# LCD.net
KiCad netlist of a schematic drawn in Altium Designer
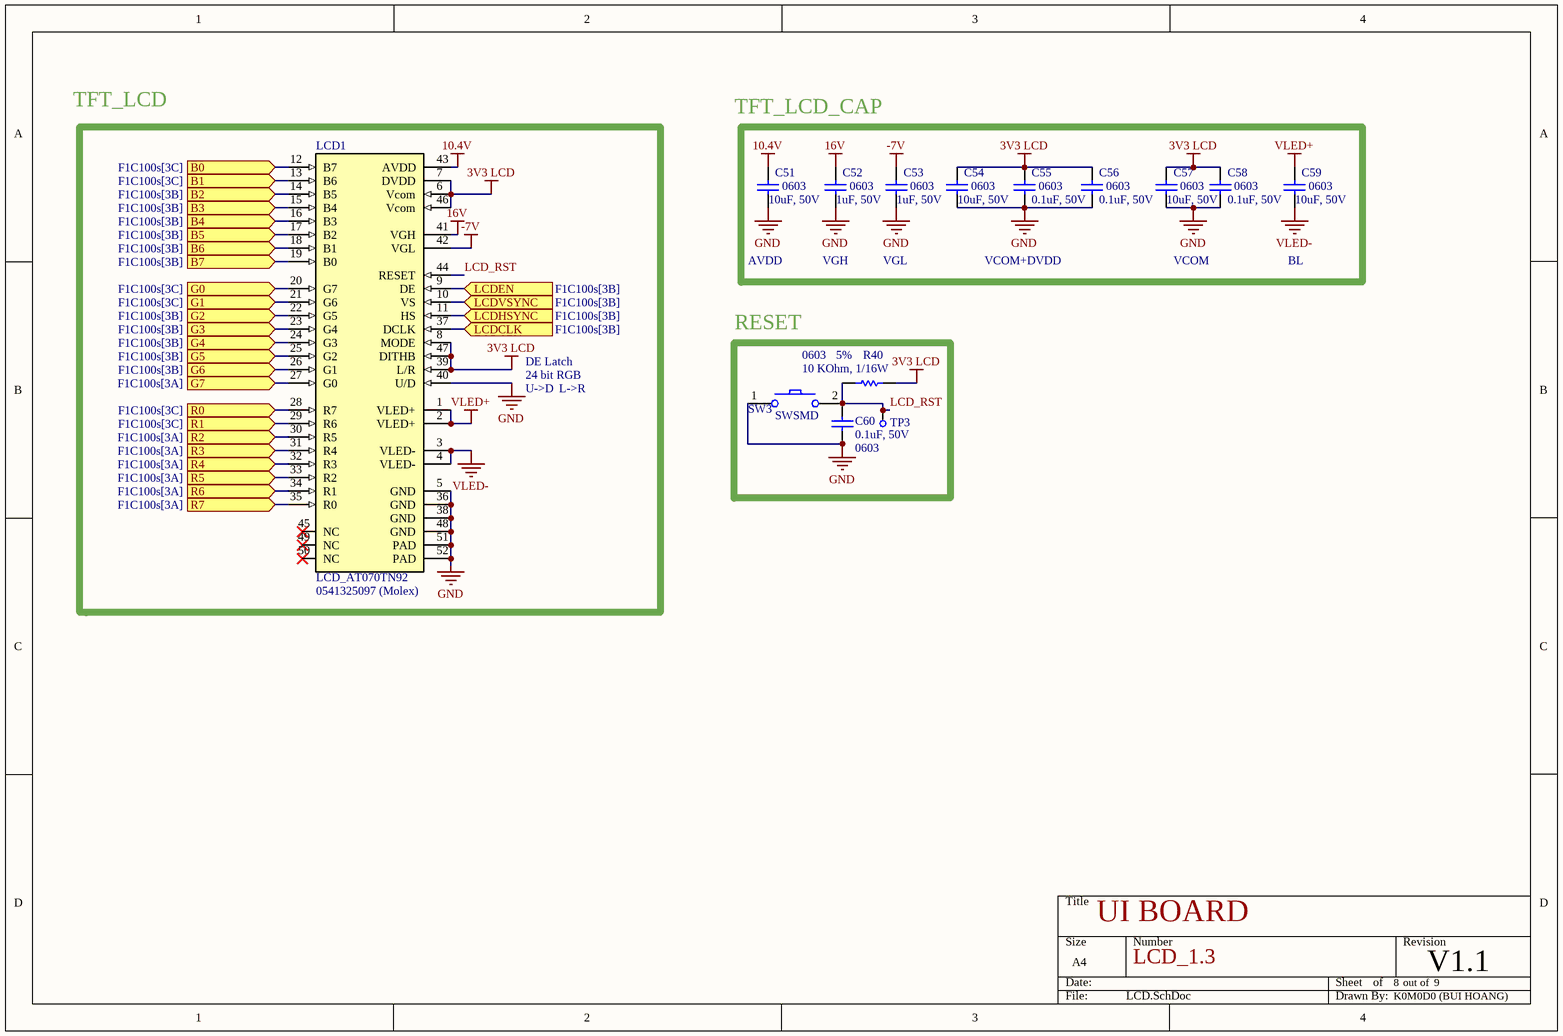
[diagram p0: LCD.SchDoc]

(export (version "E")
  (design (tool "Eeschema 10.0.6"))
  (components
    (comp (ref "C51")
      (value "10uF, 50V")
      (footprint "C_0603")
      (description "CAP_0603")
      (fields (field (name "PACKAGE") "0603"))
      (libsource (lib "DisplayLib") (part "CAP_0603"))
    )
    (comp (ref "C52")
      (value "1uF, 50V")
      (footprint "C_0603")
      (description "CAP_0603")
      (fields (field (name "PACKAGE") "0603"))
      (libsource (lib "DisplayLib") (part "CAP_0603"))
    )
    (comp (ref "C53")
      (value "1uF, 50V")
      (footprint "C_0603")
      (description "CAP_0603")
      (fields (field (name "PACKAGE") "0603"))
      (libsource (lib "DisplayLib") (part "CAP_0603"))
    )
    (comp (ref "C54")
      (value "10uF, 50V")
      (footprint "C_0603")
      (description "CAP_0603")
      (fields (field (name "PACKAGE") "0603"))
      (libsource (lib "DisplayLib") (part "CAP_0603"))
    )
    (comp (ref "C55")
      (value "0.1uF, 50V")
      (footprint "C_0603")
      (description "CAP_0603")
      (fields (field (name "PACKAGE") "0603"))
      (libsource (lib "DisplayLib") (part "CAP_0603"))
    )
    (comp (ref "C56")
      (value "0.1uF, 50V")
      (footprint "C_0603")
      (description "CAP_0603")
      (fields (field (name "PACKAGE") "0603"))
      (libsource (lib "DisplayLib") (part "CAP_0603"))
    )
    (comp (ref "C57")
      (value "10uF, 50V")
      (footprint "C_0603")
      (description "CAP_0603")
      (fields (field (name "PACKAGE") "0603"))
      (libsource (lib "DisplayLib") (part "CAP_0603"))
    )
    (comp (ref "C58")
      (value "0.1uF, 50V")
      (footprint "C_0603")
      (description "CAP_0603")
      (fields (field (name "PACKAGE") "0603"))
      (libsource (lib "DisplayLib") (part "CAP_0603"))
    )
    (comp (ref "C59")
      (value "10uF, 50V")
      (footprint "C_0603")
      (description "CAP_0603")
      (fields (field (name "PACKAGE") "0603"))
      (libsource (lib "DisplayLib") (part "CAP_0603"))
    )
    (comp (ref "C60")
      (value "0.1uF, 50V")
      (footprint "C_0603")
      (description "CAP_0603")
      (fields (field (name "PACKAGE") "0603"))
      (libsource (lib "DisplayLib") (part "CAP_0603"))
    )
    (comp (ref "LCD1")
      (value "LCD_AT070TN92")
      (footprint "CONN_LCD_AT070TN90")
      (description "LCD 7 inch (800 x 3(RGB) x 480) RES\r\n__NOTE THAT THIS IS FFC 50PINS CONN w/ THE LCD FOOTPRINT!__")
      (fields (field (name "CONNECTOR PART NUMBER") "0541325097 (Molex)"))
      (libsource (lib "DisplayLib") (part "LCD_AT070TN92"))
    )
    (comp (ref "R40")
      (value "10 KOhm, 1/16W")
      (footprint "R_0603")
      (description "RES_0603")
      (fields (field (name "PACKAGE") "0603") (field (name "ACC") "5%"))
      (libsource (lib "DisplayLib") (part "RES_0603"))
    )
    (comp (ref "SW3")
      (value "SWSMD")
      (footprint "SW_SMD_NOGND")
      (description "SW_SMD")
      (libsource (lib "DisplayLib") (part "SWSMD_NOGND"))
    )
    (comp (ref "TP3")
      (value "TESTPT")
      (footprint "TESTPT")
      (description "Test point")
      (libsource (lib "DisplayLib") (part "TESTPT"))
    )
  )
  (nets
    (net (code "1") (name "-7V") (class "Default")
      (node (ref "C53") (pin "2") (pinfunction "2_2") (pintype "passive"))
      (node (ref "LCD1") (pin "42") (pinfunction "VGL_42") (pintype "power_in"))
    )
    (net (code "2") (name "/B0") (class "Default")
      (node (ref "LCD1") (pin "12") (pinfunction "B7_12") (pintype "input"))
    )
    (net (code "3") (name "/B1") (class "Default")
      (node (ref "LCD1") (pin "13") (pinfunction "B6_13") (pintype "input"))
    )
    (net (code "4") (name "/B2") (class "Default")
      (node (ref "LCD1") (pin "14") (pinfunction "B5_14") (pintype "input"))
    )
    (net (code "5") (name "/B3") (class "Default")
      (node (ref "LCD1") (pin "15") (pinfunction "B4_15") (pintype "input"))
    )
    (net (code "6") (name "/B4") (class "Default")
      (node (ref "LCD1") (pin "16") (pinfunction "B3_16") (pintype "input"))
    )
    (net (code "7") (name "/B5") (class "Default")
      (node (ref "LCD1") (pin "17") (pinfunction "B2_17") (pintype "input"))
    )
    (net (code "8") (name "/B6") (class "Default")
      (node (ref "LCD1") (pin "18") (pinfunction "B1_18") (pintype "input"))
    )
    (net (code "9") (name "/B7") (class "Default")
      (node (ref "LCD1") (pin "19") (pinfunction "B0_19") (pintype "input"))
    )
    (net (code "10") (name "/G0") (class "Default")
      (node (ref "LCD1") (pin "20") (pinfunction "G7_20") (pintype "input"))
    )
    (net (code "11") (name "/G1") (class "Default")
      (node (ref "LCD1") (pin "21") (pinfunction "G6_21") (pintype "input"))
    )
    (net (code "12") (name "/G2") (class "Default")
      (node (ref "LCD1") (pin "22") (pinfunction "G5_22") (pintype "input"))
    )
    (net (code "13") (name "/G3") (class "Default")
      (node (ref "LCD1") (pin "23") (pinfunction "G4_23") (pintype "input"))
    )
    (net (code "14") (name "/G4") (class "Default")
      (node (ref "LCD1") (pin "24") (pinfunction "G3_24") (pintype "input"))
    )
    (net (code "15") (name "/G5") (class "Default")
      (node (ref "LCD1") (pin "25") (pinfunction "G2_25") (pintype "input"))
    )
    (net (code "16") (name "/G6") (class "Default")
      (node (ref "LCD1") (pin "26") (pinfunction "G1_26") (pintype "input"))
    )
    (net (code "17") (name "/G7") (class "Default")
      (node (ref "LCD1") (pin "27") (pinfunction "G0_27") (pintype "input"))
    )
    (net (code "18") (name "/LCDCLK") (class "Default")
      (node (ref "LCD1") (pin "37") (pinfunction "DCLK_37") (pintype "input"))
    )
    (net (code "19") (name "/LCDEN") (class "Default")
      (node (ref "LCD1") (pin "9") (pinfunction "DE_9") (pintype "input"))
    )
    (net (code "20") (name "/LCDHSYNC") (class "Default")
      (node (ref "LCD1") (pin "11") (pinfunction "HS_11") (pintype "input"))
    )
    (net (code "21") (name "/LCDVSYNC") (class "Default")
      (node (ref "LCD1") (pin "10") (pinfunction "VS_10") (pintype "input"))
    )
    (net (code "22") (name "/LCD_RST") (class "Default")
      (node (ref "C60") (pin "2") (pinfunction "2_2") (pintype "passive"))
      (node (ref "LCD1") (pin "44") (pinfunction "RESET_44") (pintype "input"))
      (node (ref "R40") (pin "1") (pinfunction "1_1") (pintype "passive"))
      (node (ref "SW3") (pin "2") (pinfunction "2_2") (pintype "passive"))
      (node (ref "TP3") (pin "1") (pinfunction "1_1") (pintype "passive"))
    )
    (net (code "23") (name "/R0") (class "Default")
      (node (ref "LCD1") (pin "28") (pinfunction "R7_28") (pintype "input"))
    )
    (net (code "24") (name "/R1") (class "Default")
      (node (ref "LCD1") (pin "29") (pinfunction "R6_29") (pintype "input"))
    )
    (net (code "25") (name "/R2") (class "Default")
      (node (ref "LCD1") (pin "30") (pinfunction "R5_30") (pintype "input"))
    )
    (net (code "26") (name "/R3") (class "Default")
      (node (ref "LCD1") (pin "31") (pinfunction "R4_31") (pintype "input"))
    )
    (net (code "27") (name "/R4") (class "Default")
      (node (ref "LCD1") (pin "32") (pinfunction "R3_32") (pintype "input"))
    )
    (net (code "28") (name "/R5") (class "Default")
      (node (ref "LCD1") (pin "33") (pinfunction "R2_33") (pintype "input"))
    )
    (net (code "29") (name "/R6") (class "Default")
      (node (ref "LCD1") (pin "34") (pinfunction "R1_34") (pintype "input"))
    )
    (net (code "30") (name "/R7") (class "Default")
      (node (ref "LCD1") (pin "35") (pinfunction "R0_35") (pintype "input"))
    )
    (net (code "31") (name "3V3 LCD") (class "Default")
      (node (ref "C54") (pin "2") (pinfunction "2_2") (pintype "passive"))
      (node (ref "C55") (pin "2") (pinfunction "2_2") (pintype "passive"))
      (node (ref "C56") (pin "2") (pinfunction "2_2") (pintype "passive"))
      (node (ref "C57") (pin "2") (pinfunction "2_2") (pintype "passive"))
      (node (ref "C58") (pin "2") (pinfunction "2_2") (pintype "passive"))
      (node (ref "LCD1") (pin "39") (pinfunction "L/R_39") (pintype "input"))
      (node (ref "LCD1") (pin "46") (pinfunction "Vcom_46") (pintype "input"))
      (node (ref "LCD1") (pin "47") (pinfunction "DITHB_47") (pintype "input"))
      (node (ref "LCD1") (pin "6") (pinfunction "Vcom_6") (pintype "input"))
      (node (ref "LCD1") (pin "7") (pinfunction "DVDD_7") (pintype "power_in"))
      (node (ref "LCD1") (pin "8") (pinfunction "MODE_8") (pintype "input"))
      (node (ref "R40") (pin "2") (pinfunction "2_2") (pintype "passive"))
    )
    (net (code "32") (name "10.4V") (class "Default")
      (node (ref "C51") (pin "2") (pinfunction "2_2") (pintype "passive"))
      (node (ref "LCD1") (pin "43") (pinfunction "AVDD_43") (pintype "power_in"))
    )
    (net (code "33") (name "16V") (class "Default")
      (node (ref "C52") (pin "2") (pinfunction "2_2") (pintype "passive"))
      (node (ref "LCD1") (pin "41") (pinfunction "VGH_41") (pintype "power_in"))
    )
    (net (code "34") (name "GND") (class "Default")
      (node (ref "C51") (pin "1") (pinfunction "1_1") (pintype "passive"))
      (node (ref "C52") (pin "1") (pinfunction "1_1") (pintype "passive"))
      (node (ref "C53") (pin "1") (pinfunction "1_1") (pintype "passive"))
      (node (ref "C54") (pin "1") (pinfunction "1_1") (pintype "passive"))
      (node (ref "C55") (pin "1") (pinfunction "1_1") (pintype "passive"))
      (node (ref "C56") (pin "1") (pinfunction "1_1") (pintype "passive"))
      (node (ref "C57") (pin "1") (pinfunction "1_1") (pintype "passive"))
      (node (ref "C58") (pin "1") (pinfunction "1_1") (pintype "passive"))
      (node (ref "C60") (pin "1") (pinfunction "1_1") (pintype "passive"))
      (node (ref "LCD1") (pin "36") (pinfunction "GND_36") (pintype "power_in"))
      (node (ref "LCD1") (pin "38") (pinfunction "GND_38") (pintype "power_in"))
      (node (ref "LCD1") (pin "40") (pinfunction "U/D_40") (pintype "input"))
      (node (ref "LCD1") (pin "48") (pinfunction "GND_48") (pintype "power_in"))
      (node (ref "LCD1") (pin "5") (pinfunction "GND_5") (pintype "power_in"))
      (node (ref "LCD1") (pin "51") (pinfunction "PAD_51") (pintype "power_in"))
      (node (ref "LCD1") (pin "52") (pinfunction "PAD_52") (pintype "power_in"))
      (node (ref "SW3") (pin "1") (pinfunction "1_1") (pintype "passive"))
    )
    (net (code "35") (name "VLED+") (class "Default")
      (node (ref "C59") (pin "2") (pinfunction "2_2") (pintype "passive"))
      (node (ref "LCD1") (pin "1") (pinfunction "VLED+_1") (pintype "power_in"))
      (node (ref "LCD1") (pin "2") (pinfunction "VLED+_2") (pintype "power_in"))
    )
    (net (code "36") (name "VLED-") (class "Default")
      (node (ref "C59") (pin "1") (pinfunction "1_1") (pintype "passive"))
      (node (ref "LCD1") (pin "3") (pinfunction "VLED-_3") (pintype "power_in"))
      (node (ref "LCD1") (pin "4") (pinfunction "VLED-_4") (pintype "power_in"))
    )
    (net (code "37") (name "unconnected-(LCD1-NC-Pad45)") (class "Default")
      (node (ref "LCD1") (pin "45") (pinfunction "NC_45") (pintype "passive+no_connect"))
    )
    (net (code "38") (name "unconnected-(LCD1-NC-Pad49)") (class "Default")
      (node (ref "LCD1") (pin "49") (pinfunction "NC_49") (pintype "passive+no_connect"))
    )
    (net (code "39") (name "unconnected-(LCD1-NC-Pad50)") (class "Default")
      (node (ref "LCD1") (pin "50") (pinfunction "NC_50") (pintype "passive+no_connect"))
    )
  )
)
